# CC_capteurs.net
KiCad netlist of a schematic drawn in Altium Designer
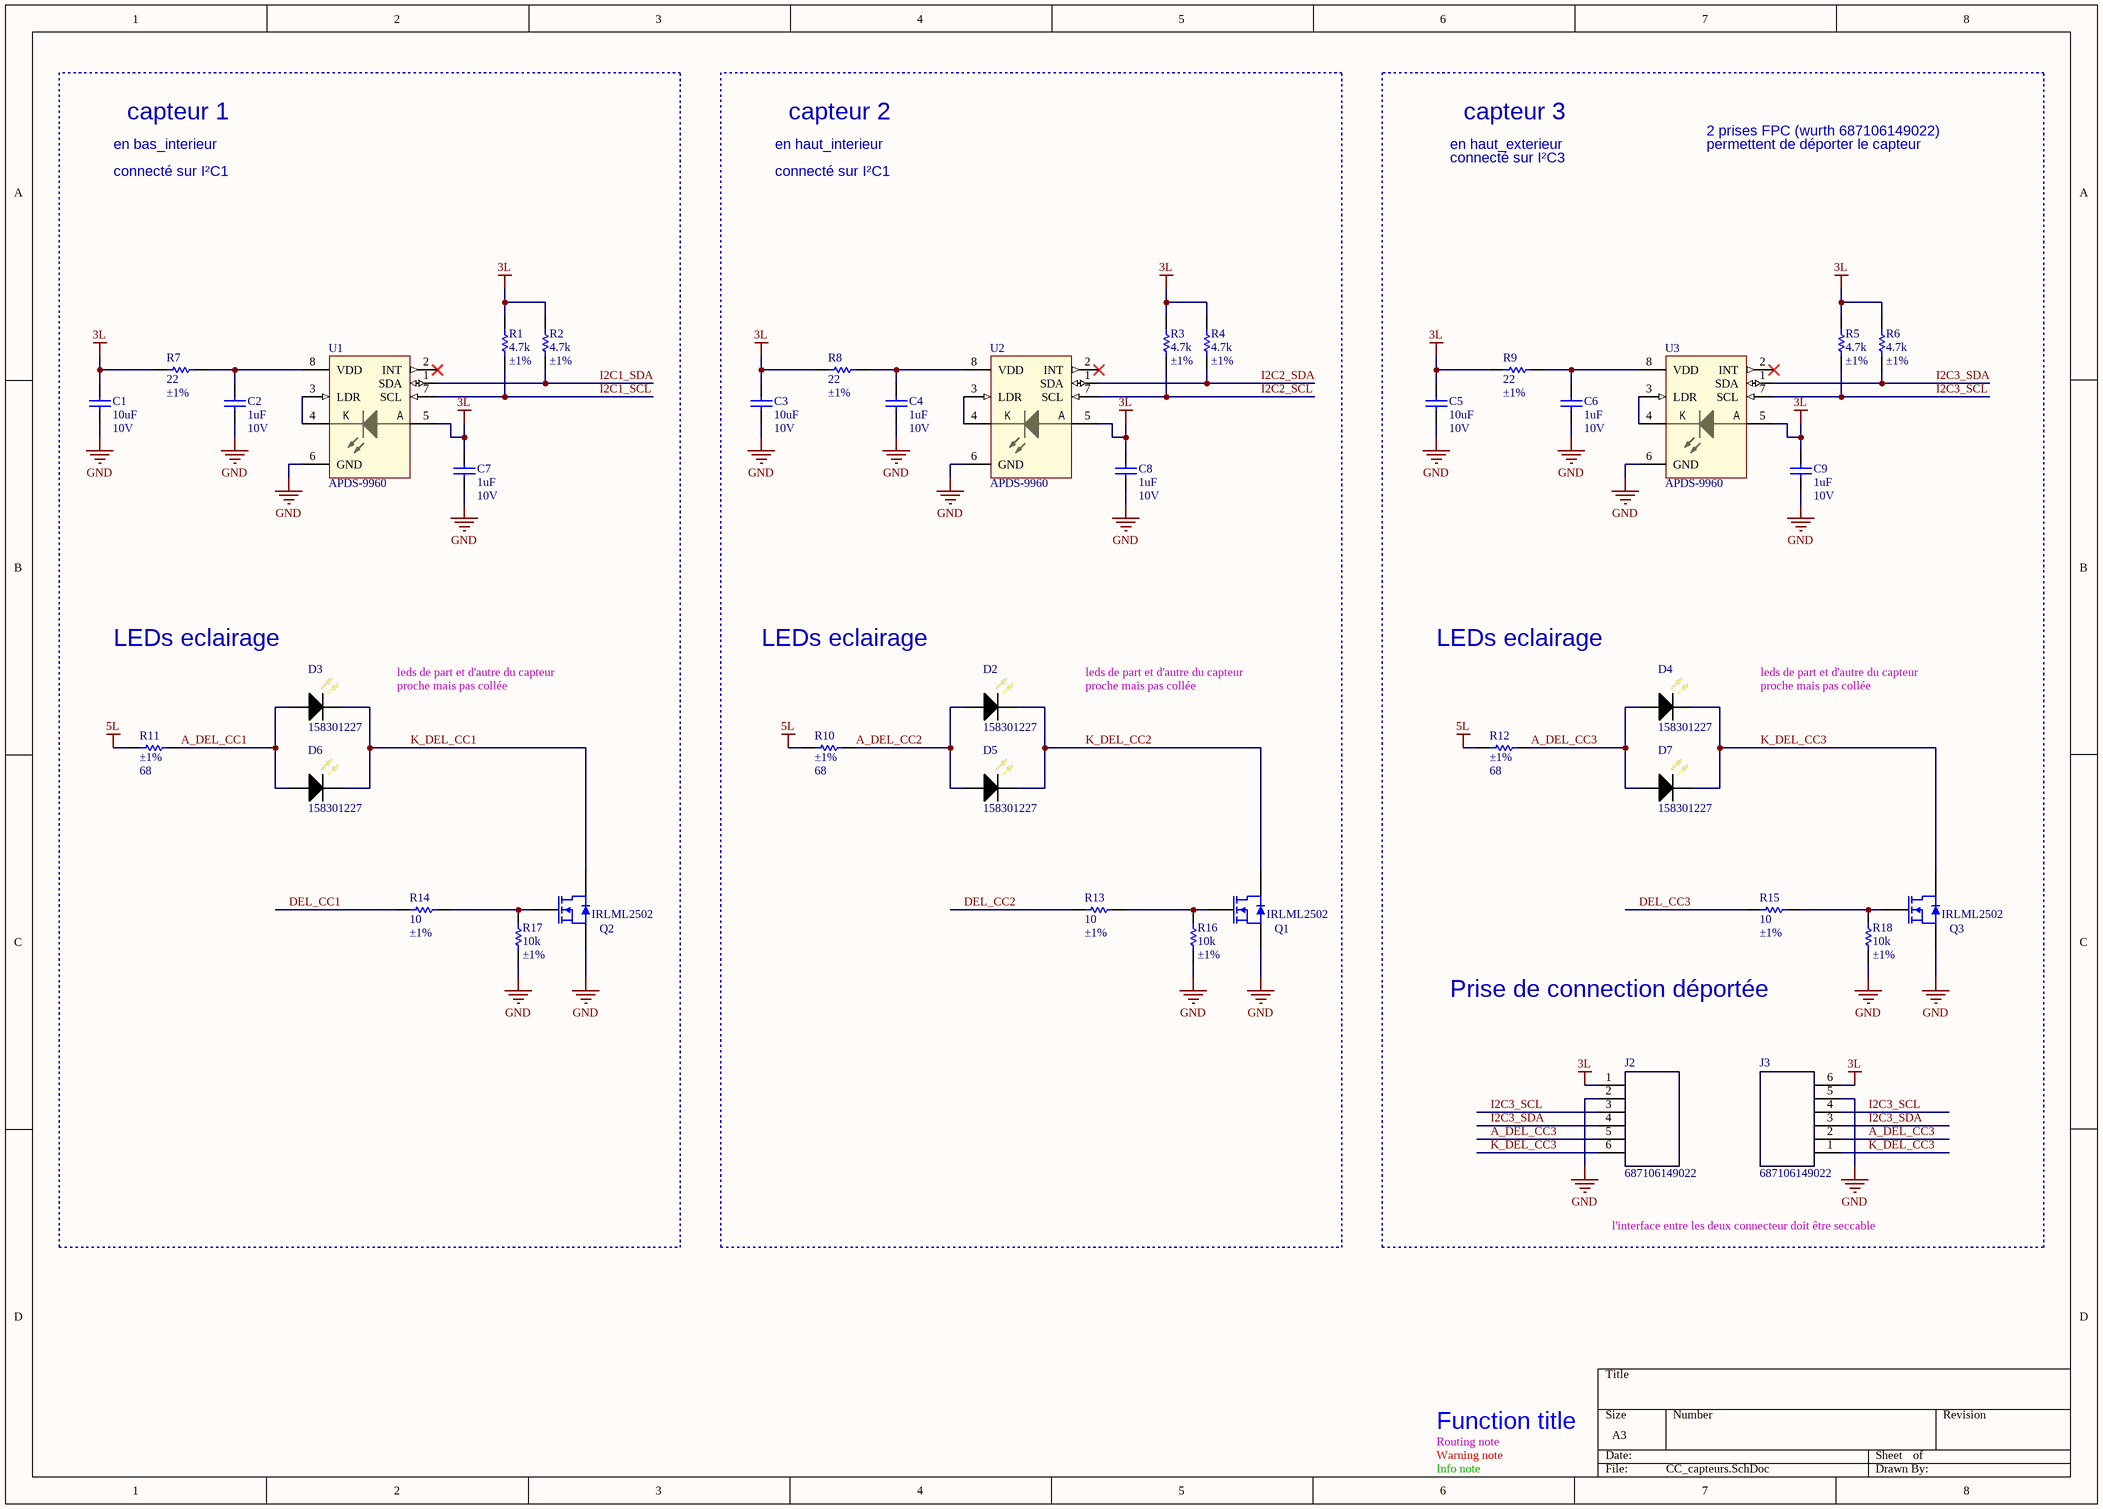
[diagram p0: CC_capteurs.SchDoc]

(export (version "E")
  (design (tool "Eeschema 10.0.6"))
  (components
    (comp (ref "C1")
      (value "10uF")
      (footprint "WCAP-CSGP_0805, 2x1.25x1.25")
      (description "CAP CER 10uF 10V X7R 0805")
      (fields
        (field (name "MANUFACTURER") "Wurth Elektronik")
        (field (name "MANUFACTURER PART NUMBER") "885012207026")
        (field (name "RATEDVOLTAGE") "10V")
      )
      (libsource (lib "Condensateur") (part "WCAP-CSGP, 885012207026"))
    )
    (comp (ref "C2")
      (value "1uF")
      (footprint "WCAP-CSGP_0402, 1x0.5x0.5")
      (description "CAP CER 1UF 10V X5R 0402")
      (fields
        (field (name "MANUFACTURER") "Wurth Elektronik")
        (field (name "MANUFACTURER PART NUMBER") "885012105012")
        (field (name "RATEDVOLTAGE") "10V")
      )
      (libsource (lib "Condensateur") (part "WCAP-CSGP, 885012105012"))
    )
    (comp (ref "C3")
      (value "10uF")
      (footprint "WCAP-CSGP_0805, 2x1.25x1.25")
      (description "CAP CER 10uF 10V X7R 0805")
      (fields
        (field (name "MANUFACTURER") "Wurth Elektronik")
        (field (name "MANUFACTURER PART NUMBER") "885012207026")
        (field (name "RATEDVOLTAGE") "10V")
      )
      (libsource (lib "Condensateur") (part "WCAP-CSGP, 885012207026"))
    )
    (comp (ref "C4")
      (value "1uF")
      (footprint "WCAP-CSGP_0402, 1x0.5x0.5")
      (description "CAP CER 1UF 10V X5R 0402")
      (fields
        (field (name "MANUFACTURER") "Wurth Elektronik")
        (field (name "MANUFACTURER PART NUMBER") "885012105012")
        (field (name "RATEDVOLTAGE") "10V")
      )
      (libsource (lib "Condensateur") (part "WCAP-CSGP, 885012105012"))
    )
    (comp (ref "C5")
      (value "10uF")
      (footprint "WCAP-CSGP_0805, 2x1.25x1.25")
      (description "CAP CER 10uF 10V X7R 0805")
      (fields
        (field (name "MANUFACTURER") "Wurth Elektronik")
        (field (name "MANUFACTURER PART NUMBER") "885012207026")
        (field (name "RATEDVOLTAGE") "10V")
      )
      (libsource (lib "Condensateur") (part "WCAP-CSGP, 885012207026"))
    )
    (comp (ref "C6")
      (value "1uF")
      (footprint "WCAP-CSGP_0402, 1x0.5x0.5")
      (description "CAP CER 1UF 10V X5R 0402")
      (fields
        (field (name "MANUFACTURER") "Wurth Elektronik")
        (field (name "MANUFACTURER PART NUMBER") "885012105012")
        (field (name "RATEDVOLTAGE") "10V")
      )
      (libsource (lib "Condensateur") (part "WCAP-CSGP, 885012105012"))
    )
    (comp (ref "C7")
      (value "1uF")
      (footprint "WCAP-CSGP_0402, 1x0.5x0.5")
      (description "CAP CER 1UF 10V X5R 0402")
      (fields
        (field (name "MANUFACTURER") "Wurth Elektronik")
        (field (name "MANUFACTURER PART NUMBER") "885012105012")
        (field (name "RATEDVOLTAGE") "10V")
      )
      (libsource (lib "Condensateur") (part "WCAP-CSGP, 885012105012"))
    )
    (comp (ref "C8")
      (value "1uF")
      (footprint "WCAP-CSGP_0402, 1x0.5x0.5")
      (description "CAP CER 1UF 10V X5R 0402")
      (fields
        (field (name "MANUFACTURER") "Wurth Elektronik")
        (field (name "MANUFACTURER PART NUMBER") "885012105012")
        (field (name "RATEDVOLTAGE") "10V")
      )
      (libsource (lib "Condensateur") (part "WCAP-CSGP, 885012105012"))
    )
    (comp (ref "C9")
      (value "1uF")
      (footprint "WCAP-CSGP_0402, 1x0.5x0.5")
      (description "CAP CER 1UF 10V X5R 0402")
      (fields
        (field (name "MANUFACTURER") "Wurth Elektronik")
        (field (name "MANUFACTURER PART NUMBER") "885012105012")
        (field (name "RATEDVOLTAGE") "10V")
      )
      (libsource (lib "Condensateur") (part "WCAP-CSGP, 885012105012"))
    )
    (comp (ref "D2")
      (value "158301227")
      (footprint "WL-SWTP_3014")
      (description "LED WL-SWTP WARM WHT 2700K 1206")
      (fields (field (name "MANUFACTURER") "Wurth Electronics Inc."))
      (libsource (lib "Optoélectronique") (part "158301227"))
    )
    (comp (ref "D3")
      (value "158301227")
      (footprint "WL-SWTP_3014")
      (description "LED WL-SWTP WARM WHT 2700K 1206")
      (fields (field (name "MANUFACTURER") "Wurth Electronics Inc."))
      (libsource (lib "Optoélectronique") (part "158301227"))
    )
    (comp (ref "D4")
      (value "158301227")
      (footprint "WL-SWTP_3014")
      (description "LED WL-SWTP WARM WHT 2700K 1206")
      (fields (field (name "MANUFACTURER") "Wurth Electronics Inc."))
      (libsource (lib "Optoélectronique") (part "158301227"))
    )
    (comp (ref "D5")
      (value "158301227")
      (footprint "WL-SWTP_3014")
      (description "LED WL-SWTP WARM WHT 2700K 1206")
      (fields (field (name "MANUFACTURER") "Wurth Electronics Inc."))
      (libsource (lib "Optoélectronique") (part "158301227"))
    )
    (comp (ref "D6")
      (value "158301227")
      (footprint "WL-SWTP_3014")
      (description "LED WL-SWTP WARM WHT 2700K 1206")
      (fields (field (name "MANUFACTURER") "Wurth Electronics Inc."))
      (libsource (lib "Optoélectronique") (part "158301227"))
    )
    (comp (ref "D7")
      (value "158301227")
      (footprint "WL-SWTP_3014")
      (description "LED WL-SWTP WARM WHT 2700K 1206")
      (fields (field (name "MANUFACTURER") "Wurth Electronics Inc."))
      (libsource (lib "Optoélectronique") (part "158301227"))
    )
    (comp (ref "J2")
      (value "687106149022")
      (footprint "687106149022")
      (description "CONN .5MM HORZ BOTTOM SMD 6POS")
      (fields (field (name "MANUFACTURER") "Wurth Electronics Inc."))
      (libsource (lib "Connecteurs") (part "687106149022"))
    )
    (comp (ref "J3")
      (value "687106149022")
      (footprint "687106149022")
      (description "CONN .5MM HORZ BOTTOM SMD 6POS")
      (fields (field (name "MANUFACTURER") "Wurth Electronics Inc."))
      (libsource (lib "Connecteurs") (part "687106149022"))
    )
    (comp (ref "Q1")
      (value "IRLML2502")
      (footprint "SOT-23")
      (description "MOSFET CANAL N SOT-23")
      (fields (field (name "MANUFACTURER PART NUMBER") "IRLML2502PBF"))
      (libsource (lib "Transistors") (part "IRLML2502"))
    )
    (comp (ref "Q2")
      (value "IRLML2502")
      (footprint "SOT-23")
      (description "MOSFET CANAL N SOT-23")
      (fields (field (name "MANUFACTURER PART NUMBER") "IRLML2502PBF"))
      (libsource (lib "Transistors") (part "IRLML2502"))
    )
    (comp (ref "Q3")
      (value "IRLML2502")
      (footprint "SOT-23")
      (description "MOSFET CANAL N SOT-23")
      (fields (field (name "MANUFACTURER PART NUMBER") "IRLML2502PBF"))
      (libsource (lib "Transistors") (part "IRLML2502"))
    )
    (comp (ref "R1")
      (value "4.7k")
      (footprint "RESC1005X04N")
      (description "RES SMD 4K7 OHM 1% 1/16W 0402")
      (fields
        (field (name "POWER") "63mW")
        (field (name "MANUFACTURER") "Yageo")
        (field (name "PRECISION") "±1%")
      )
      (libsource (lib "Resistance") (part "RC0402FR-074K7L"))
    )
    (comp (ref "R2")
      (value "4.7k")
      (footprint "RESC1005X04N")
      (description "RES SMD 4K7 OHM 1% 1/16W 0402")
      (fields
        (field (name "POWER") "63mW")
        (field (name "MANUFACTURER") "Yageo")
        (field (name "PRECISION") "±1%")
      )
      (libsource (lib "Resistance") (part "RC0402FR-074K7L"))
    )
    (comp (ref "R3")
      (value "4.7k")
      (footprint "RESC1005X04N")
      (description "RES SMD 4K7 OHM 1% 1/16W 0402")
      (fields
        (field (name "POWER") "63mW")
        (field (name "MANUFACTURER") "Yageo")
        (field (name "PRECISION") "±1%")
      )
      (libsource (lib "Resistance") (part "RC0402FR-074K7L"))
    )
    (comp (ref "R4")
      (value "4.7k")
      (footprint "RESC1005X04N")
      (description "RES SMD 4K7 OHM 1% 1/16W 0402")
      (fields
        (field (name "POWER") "63mW")
        (field (name "MANUFACTURER") "Yageo")
        (field (name "PRECISION") "±1%")
      )
      (libsource (lib "Resistance") (part "RC0402FR-074K7L"))
    )
    (comp (ref "R5")
      (value "4.7k")
      (footprint "RESC1005X04N")
      (description "RES SMD 4K7 OHM 1% 1/16W 0402")
      (fields
        (field (name "POWER") "63mW")
        (field (name "MANUFACTURER") "Yageo")
        (field (name "PRECISION") "±1%")
      )
      (libsource (lib "Resistance") (part "RC0402FR-074K7L"))
    )
    (comp (ref "R6")
      (value "4.7k")
      (footprint "RESC1005X04N")
      (description "RES SMD 4K7 OHM 1% 1/16W 0402")
      (fields
        (field (name "POWER") "63mW")
        (field (name "MANUFACTURER") "Yageo")
        (field (name "PRECISION") "±1%")
      )
      (libsource (lib "Resistance") (part "RC0402FR-074K7L"))
    )
    (comp (ref "R7")
      (value "22")
      (footprint "RESC1005X04N")
      (description "RES SMD 22 OHM 1% 1/16W 0402")
      (fields
        (field (name "POWER") "63mW")
        (field (name "MANUFACTURER") "Yageo")
        (field (name "PRECISION") "±1%")
      )
      (libsource (lib "Resistance") (part "RC0402FR-0722RL"))
    )
    (comp (ref "R8")
      (value "22")
      (footprint "RESC1005X04N")
      (description "RES SMD 22 OHM 1% 1/16W 0402")
      (fields
        (field (name "POWER") "63mW")
        (field (name "MANUFACTURER") "Yageo")
        (field (name "PRECISION") "±1%")
      )
      (libsource (lib "Resistance") (part "RC0402FR-0722RL"))
    )
    (comp (ref "R9")
      (value "22")
      (footprint "RESC1005X04N")
      (description "RES SMD 22 OHM 1% 1/16W 0402")
      (fields
        (field (name "POWER") "63mW")
        (field (name "MANUFACTURER") "Yageo")
        (field (name "PRECISION") "±1%")
      )
      (libsource (lib "Resistance") (part "RC0402FR-0722RL"))
    )
    (comp (ref "R10")
      (value "68")
      (footprint "RESC1608X06N")
      (description "RES SMD 68 OHM 1% 1/10W 0603")
      (fields
        (field (name "MANUFACTURER") "Yageo")
        (field (name "MANUFACTURER PART NUMBER") "RC0603FR-0768RL")
        (field (name "PRECISION") "±1%")
      )
      (libsource (lib "Resistance") (part "RC0603FR-0768RL"))
    )
    (comp (ref "R11")
      (value "68")
      (footprint "RESC1608X06N")
      (description "RES SMD 68 OHM 1% 1/10W 0603")
      (fields
        (field (name "MANUFACTURER") "Yageo")
        (field (name "MANUFACTURER PART NUMBER") "RC0603FR-0768RL")
        (field (name "PRECISION") "±1%")
      )
      (libsource (lib "Resistance") (part "RC0603FR-0768RL"))
    )
    (comp (ref "R12")
      (value "68")
      (footprint "RESC1608X06N")
      (description "RES SMD 68 OHM 1% 1/10W 0603")
      (fields
        (field (name "MANUFACTURER") "Yageo")
        (field (name "MANUFACTURER PART NUMBER") "RC0603FR-0768RL")
        (field (name "PRECISION") "±1%")
      )
      (libsource (lib "Resistance") (part "RC0603FR-0768RL"))
    )
    (comp (ref "R13")
      (value "10")
      (footprint "RESC1005X04N")
      (description "RES SMD 10 OHM 1% 1/16W 0402")
      (fields
        (field (name "POWER") "63mW")
        (field (name "MANUFACTURER") "Yageo")
        (field (name "PRECISION") "±1%")
      )
      (libsource (lib "Resistance") (part "RC0402FR-0710RL"))
    )
    (comp (ref "R14")
      (value "10")
      (footprint "RESC1005X04N")
      (description "RES SMD 10 OHM 1% 1/16W 0402")
      (fields
        (field (name "POWER") "63mW")
        (field (name "MANUFACTURER") "Yageo")
        (field (name "PRECISION") "±1%")
      )
      (libsource (lib "Resistance") (part "RC0402FR-0710RL"))
    )
    (comp (ref "R15")
      (value "10")
      (footprint "RESC1005X04N")
      (description "RES SMD 10 OHM 1% 1/16W 0402")
      (fields
        (field (name "POWER") "63mW")
        (field (name "MANUFACTURER") "Yageo")
        (field (name "PRECISION") "±1%")
      )
      (libsource (lib "Resistance") (part "RC0402FR-0710RL"))
    )
    (comp (ref "R16")
      (value "10k")
      (footprint "RESC1005X04N")
      (description "RES SMD 10K OHM 1% 1/16W 0402")
      (fields
        (field (name "POWER") "63mW")
        (field (name "MANUFACTURER") "Yageo")
        (field (name "PRECISION") "±1%")
      )
      (libsource (lib "Resistance") (part "RC0402FR-0710KL"))
    )
    (comp (ref "R17")
      (value "10k")
      (footprint "RESC1005X04N")
      (description "RES SMD 10K OHM 1% 1/16W 0402")
      (fields
        (field (name "POWER") "63mW")
        (field (name "MANUFACTURER") "Yageo")
        (field (name "PRECISION") "±1%")
      )
      (libsource (lib "Resistance") (part "RC0402FR-0710KL"))
    )
    (comp (ref "R18")
      (value "10k")
      (footprint "RESC1005X04N")
      (description "RES SMD 10K OHM 1% 1/16W 0402")
      (fields
        (field (name "POWER") "63mW")
        (field (name "MANUFACTURER") "Yageo")
        (field (name "PRECISION") "±1%")
      )
      (libsource (lib "Resistance") (part "RC0402FR-0710KL"))
    )
    (comp (ref "U1")
      (value "APDS-9960")
      (footprint "APDS996X")
      (description "Digital Proximity, Ambient Light, RGB and Gesture Sensor")
      (fields (field (name "MANUFACTURER") "AVAGO TECHNOLOGIES"))
      (libsource (lib "Optoélectronique") (part "APDS9960"))
    )
    (comp (ref "U2")
      (value "APDS-9960")
      (footprint "APDS996X")
      (description "Digital Proximity, Ambient Light, RGB and Gesture Sensor")
      (fields (field (name "MANUFACTURER") "AVAGO TECHNOLOGIES"))
      (libsource (lib "Optoélectronique") (part "APDS9960"))
    )
    (comp (ref "U3")
      (value "APDS-9960")
      (footprint "APDS996X")
      (description "Digital Proximity, Ambient Light, RGB and Gesture Sensor")
      (fields (field (name "MANUFACTURER") "AVAGO TECHNOLOGIES"))
      (libsource (lib "Optoélectronique") (part "APDS9960"))
    )
  )
  (nets
    (net (code "1") (name "/A_DEL_CC1") (class "Default")
      (node (ref "D3") (pin "2") (pinfunction "A_2") (pintype "passive"))
      (node (ref "D6") (pin "2") (pinfunction "A_2") (pintype "passive"))
      (node (ref "R11") (pin "2") (pinfunction "2_2") (pintype "passive"))
    )
    (net (code "2") (name "/A_DEL_CC2") (class "Default")
      (node (ref "D2") (pin "2") (pinfunction "A_2") (pintype "passive"))
      (node (ref "D5") (pin "2") (pinfunction "A_2") (pintype "passive"))
      (node (ref "R10") (pin "2") (pinfunction "2_2") (pintype "passive"))
    )
    (net (code "3") (name "/A_DEL_CC3") (class "Default")
      (node (ref "D4") (pin "2") (pinfunction "A_2") (pintype "passive"))
      (node (ref "D7") (pin "2") (pinfunction "A_2") (pintype "passive"))
      (node (ref "J2") (pin "5") (pintype "passive"))
      (node (ref "J3") (pin "2") (pintype "passive"))
      (node (ref "R12") (pin "2") (pinfunction "2_2") (pintype "passive"))
    )
    (net (code "4") (name "/DEL_CC1") (class "Default")
      (node (ref "R14") (pin "1") (pinfunction "1_1") (pintype "passive"))
    )
    (net (code "5") (name "/DEL_CC2") (class "Default")
      (node (ref "R13") (pin "1") (pinfunction "1_1") (pintype "passive"))
    )
    (net (code "6") (name "/DEL_CC3") (class "Default")
      (node (ref "R15") (pin "1") (pinfunction "1_1") (pintype "passive"))
    )
    (net (code "7") (name "/I2C1_SCL") (class "Default")
      (node (ref "R1") (pin "2") (pinfunction "2_2") (pintype "passive"))
      (node (ref "U1") (pin "7") (pinfunction "SCL_7") (pintype "input"))
    )
    (net (code "8") (name "/I2C1_SDA") (class "Default")
      (node (ref "R2") (pin "2") (pinfunction "2_2") (pintype "passive"))
      (node (ref "U1") (pin "1") (pinfunction "SDA_1") (pintype "bidirectional"))
    )
    (net (code "9") (name "/I2C2_SCL") (class "Default")
      (node (ref "R3") (pin "2") (pinfunction "2_2") (pintype "passive"))
      (node (ref "U2") (pin "7") (pinfunction "SCL_7") (pintype "input"))
    )
    (net (code "10") (name "/I2C2_SDA") (class "Default")
      (node (ref "R4") (pin "2") (pinfunction "2_2") (pintype "passive"))
      (node (ref "U2") (pin "1") (pinfunction "SDA_1") (pintype "bidirectional"))
    )
    (net (code "11") (name "/I2C3_SCL") (class "Default")
      (node (ref "J2") (pin "3") (pintype "passive"))
      (node (ref "J3") (pin "4") (pintype "passive"))
      (node (ref "R5") (pin "2") (pinfunction "2_2") (pintype "passive"))
      (node (ref "U3") (pin "7") (pinfunction "SCL_7") (pintype "input"))
    )
    (net (code "12") (name "/I2C3_SDA") (class "Default")
      (node (ref "J2") (pin "4") (pintype "passive"))
      (node (ref "J3") (pin "3") (pintype "passive"))
      (node (ref "R6") (pin "2") (pinfunction "2_2") (pintype "passive"))
      (node (ref "U3") (pin "1") (pinfunction "SDA_1") (pintype "bidirectional"))
    )
    (net (code "13") (name "/K_DEL_CC1") (class "Default")
      (node (ref "D3") (pin "1") (pinfunction "C_1") (pintype "passive"))
      (node (ref "D6") (pin "1") (pinfunction "C_1") (pintype "passive"))
      (node (ref "Q2") (pin "3") (pinfunction "D_3") (pintype "passive"))
    )
    (net (code "14") (name "/K_DEL_CC2") (class "Default")
      (node (ref "D2") (pin "1") (pinfunction "C_1") (pintype "passive"))
      (node (ref "D5") (pin "1") (pinfunction "C_1") (pintype "passive"))
      (node (ref "Q1") (pin "3") (pinfunction "D_3") (pintype "passive"))
    )
    (net (code "15") (name "/K_DEL_CC3") (class "Default")
      (node (ref "D4") (pin "1") (pinfunction "C_1") (pintype "passive"))
      (node (ref "D7") (pin "1") (pinfunction "C_1") (pintype "passive"))
      (node (ref "J2") (pin "6") (pintype "passive"))
      (node (ref "J3") (pin "1") (pintype "passive"))
      (node (ref "Q3") (pin "3") (pinfunction "D_3") (pintype "passive"))
    )
    (net (code "16") (name "3L") (class "Default")
      (node (ref "C1") (pin "2") (pinfunction "2_2") (pintype "passive"))
      (node (ref "C3") (pin "2") (pinfunction "2_2") (pintype "passive"))
      (node (ref "C5") (pin "2") (pinfunction "2_2") (pintype "passive"))
      (node (ref "C7") (pin "2") (pinfunction "2_2") (pintype "passive"))
      (node (ref "C8") (pin "2") (pinfunction "2_2") (pintype "passive"))
      (node (ref "C9") (pin "2") (pinfunction "2_2") (pintype "passive"))
      (node (ref "J2") (pin "1") (pintype "passive"))
      (node (ref "J3") (pin "6") (pintype "passive"))
      (node (ref "R1") (pin "1") (pinfunction "1_1") (pintype "passive"))
      (node (ref "R2") (pin "1") (pinfunction "1_1") (pintype "passive"))
      (node (ref "R3") (pin "1") (pinfunction "1_1") (pintype "passive"))
      (node (ref "R4") (pin "1") (pinfunction "1_1") (pintype "passive"))
      (node (ref "R5") (pin "1") (pinfunction "1_1") (pintype "passive"))
      (node (ref "R6") (pin "1") (pinfunction "1_1") (pintype "passive"))
      (node (ref "R7") (pin "1") (pinfunction "1_1") (pintype "passive"))
      (node (ref "R8") (pin "1") (pinfunction "1_1") (pintype "passive"))
      (node (ref "R9") (pin "1") (pinfunction "1_1") (pintype "passive"))
      (node (ref "U1") (pin "5") (pinfunction "LED_A_5") (pintype "passive"))
      (node (ref "U2") (pin "5") (pinfunction "LED_A_5") (pintype "passive"))
      (node (ref "U3") (pin "5") (pinfunction "LED_A_5") (pintype "passive"))
    )
    (net (code "17") (name "5L") (class "Default")
      (node (ref "R10") (pin "1") (pinfunction "1_1") (pintype "passive"))
      (node (ref "R11") (pin "1") (pinfunction "1_1") (pintype "passive"))
      (node (ref "R12") (pin "1") (pinfunction "1_1") (pintype "passive"))
    )
    (net (code "18") (name "GND") (class "Default")
      (node (ref "C1") (pin "1") (pinfunction "1_1") (pintype "passive"))
      (node (ref "C2") (pin "1") (pinfunction "1_1") (pintype "passive"))
      (node (ref "C3") (pin "1") (pinfunction "1_1") (pintype "passive"))
      (node (ref "C4") (pin "1") (pinfunction "1_1") (pintype "passive"))
      (node (ref "C5") (pin "1") (pinfunction "1_1") (pintype "passive"))
      (node (ref "C6") (pin "1") (pinfunction "1_1") (pintype "passive"))
      (node (ref "C7") (pin "1") (pinfunction "1_1") (pintype "passive"))
      (node (ref "C8") (pin "1") (pinfunction "1_1") (pintype "passive"))
      (node (ref "C9") (pin "1") (pinfunction "1_1") (pintype "passive"))
      (node (ref "J2") (pin "2") (pintype "passive"))
      (node (ref "J3") (pin "5") (pintype "passive"))
      (node (ref "Q1") (pin "2") (pinfunction "S_2") (pintype "passive"))
      (node (ref "Q2") (pin "2") (pinfunction "S_2") (pintype "passive"))
      (node (ref "Q3") (pin "2") (pinfunction "S_2") (pintype "passive"))
      (node (ref "R16") (pin "1") (pinfunction "1_1") (pintype "passive"))
      (node (ref "R17") (pin "1") (pinfunction "1_1") (pintype "passive"))
      (node (ref "R18") (pin "1") (pinfunction "1_1") (pintype "passive"))
      (node (ref "U1") (pin "6") (pinfunction "GND_6") (pintype "power_in"))
      (node (ref "U2") (pin "6") (pinfunction "GND_6") (pintype "power_in"))
      (node (ref "U3") (pin "6") (pinfunction "GND_6") (pintype "power_in"))
    )
    (net (code "19") (name "Net-(Q1-G)") (class "Default")
      (node (ref "Q1") (pin "1") (pinfunction "G_1") (pintype "passive"))
      (node (ref "R13") (pin "2") (pinfunction "2_2") (pintype "passive"))
      (node (ref "R16") (pin "2") (pinfunction "2_2") (pintype "passive"))
    )
    (net (code "20") (name "Net-(Q2-G)") (class "Default")
      (node (ref "Q2") (pin "1") (pinfunction "G_1") (pintype "passive"))
      (node (ref "R14") (pin "2") (pinfunction "2_2") (pintype "passive"))
      (node (ref "R17") (pin "2") (pinfunction "2_2") (pintype "passive"))
    )
    (net (code "21") (name "Net-(Q3-G)") (class "Default")
      (node (ref "Q3") (pin "1") (pinfunction "G_1") (pintype "passive"))
      (node (ref "R15") (pin "2") (pinfunction "2_2") (pintype "passive"))
      (node (ref "R18") (pin "2") (pinfunction "2_2") (pintype "passive"))
    )
    (net (code "22") (name "Net-(U1-LDR)") (class "Default")
      (node (ref "U1") (pin "3") (pinfunction "LDR_3") (pintype "input"))
      (node (ref "U1") (pin "4") (pinfunction "LED_K_4") (pintype "passive"))
    )
    (net (code "23") (name "Net-(U1-VDD)") (class "Default")
      (node (ref "C2") (pin "2") (pinfunction "2_2") (pintype "passive"))
      (node (ref "R7") (pin "2") (pinfunction "2_2") (pintype "passive"))
      (node (ref "U1") (pin "8") (pinfunction "VDD_8") (pintype "power_in"))
    )
    (net (code "24") (name "Net-(U2-LDR)") (class "Default")
      (node (ref "U2") (pin "3") (pinfunction "LDR_3") (pintype "input"))
      (node (ref "U2") (pin "4") (pinfunction "LED_K_4") (pintype "passive"))
    )
    (net (code "25") (name "Net-(U2-VDD)") (class "Default")
      (node (ref "C4") (pin "2") (pinfunction "2_2") (pintype "passive"))
      (node (ref "R8") (pin "2") (pinfunction "2_2") (pintype "passive"))
      (node (ref "U2") (pin "8") (pinfunction "VDD_8") (pintype "power_in"))
    )
    (net (code "26") (name "Net-(U3-LDR)") (class "Default")
      (node (ref "U3") (pin "3") (pinfunction "LDR_3") (pintype "input"))
      (node (ref "U3") (pin "4") (pinfunction "LED_K_4") (pintype "passive"))
    )
    (net (code "27") (name "Net-(U3-VDD)") (class "Default")
      (node (ref "C6") (pin "2") (pinfunction "2_2") (pintype "passive"))
      (node (ref "R9") (pin "2") (pinfunction "2_2") (pintype "passive"))
      (node (ref "U3") (pin "8") (pinfunction "VDD_8") (pintype "power_in"))
    )
    (net (code "28") (name "unconnected-(U1-INT-Pad2)") (class "Default")
      (node (ref "U1") (pin "2") (pinfunction "INT_2") (pintype "output+no_connect"))
    )
    (net (code "29") (name "unconnected-(U2-INT-Pad2)") (class "Default")
      (node (ref "U2") (pin "2") (pinfunction "INT_2") (pintype "output+no_connect"))
    )
    (net (code "30") (name "unconnected-(U3-INT-Pad2)") (class "Default")
      (node (ref "U3") (pin "2") (pinfunction "INT_2") (pintype "output+no_connect"))
    )
  )
)
